# gate.net
KiCad netlist of a schematic drawn in EAGLE
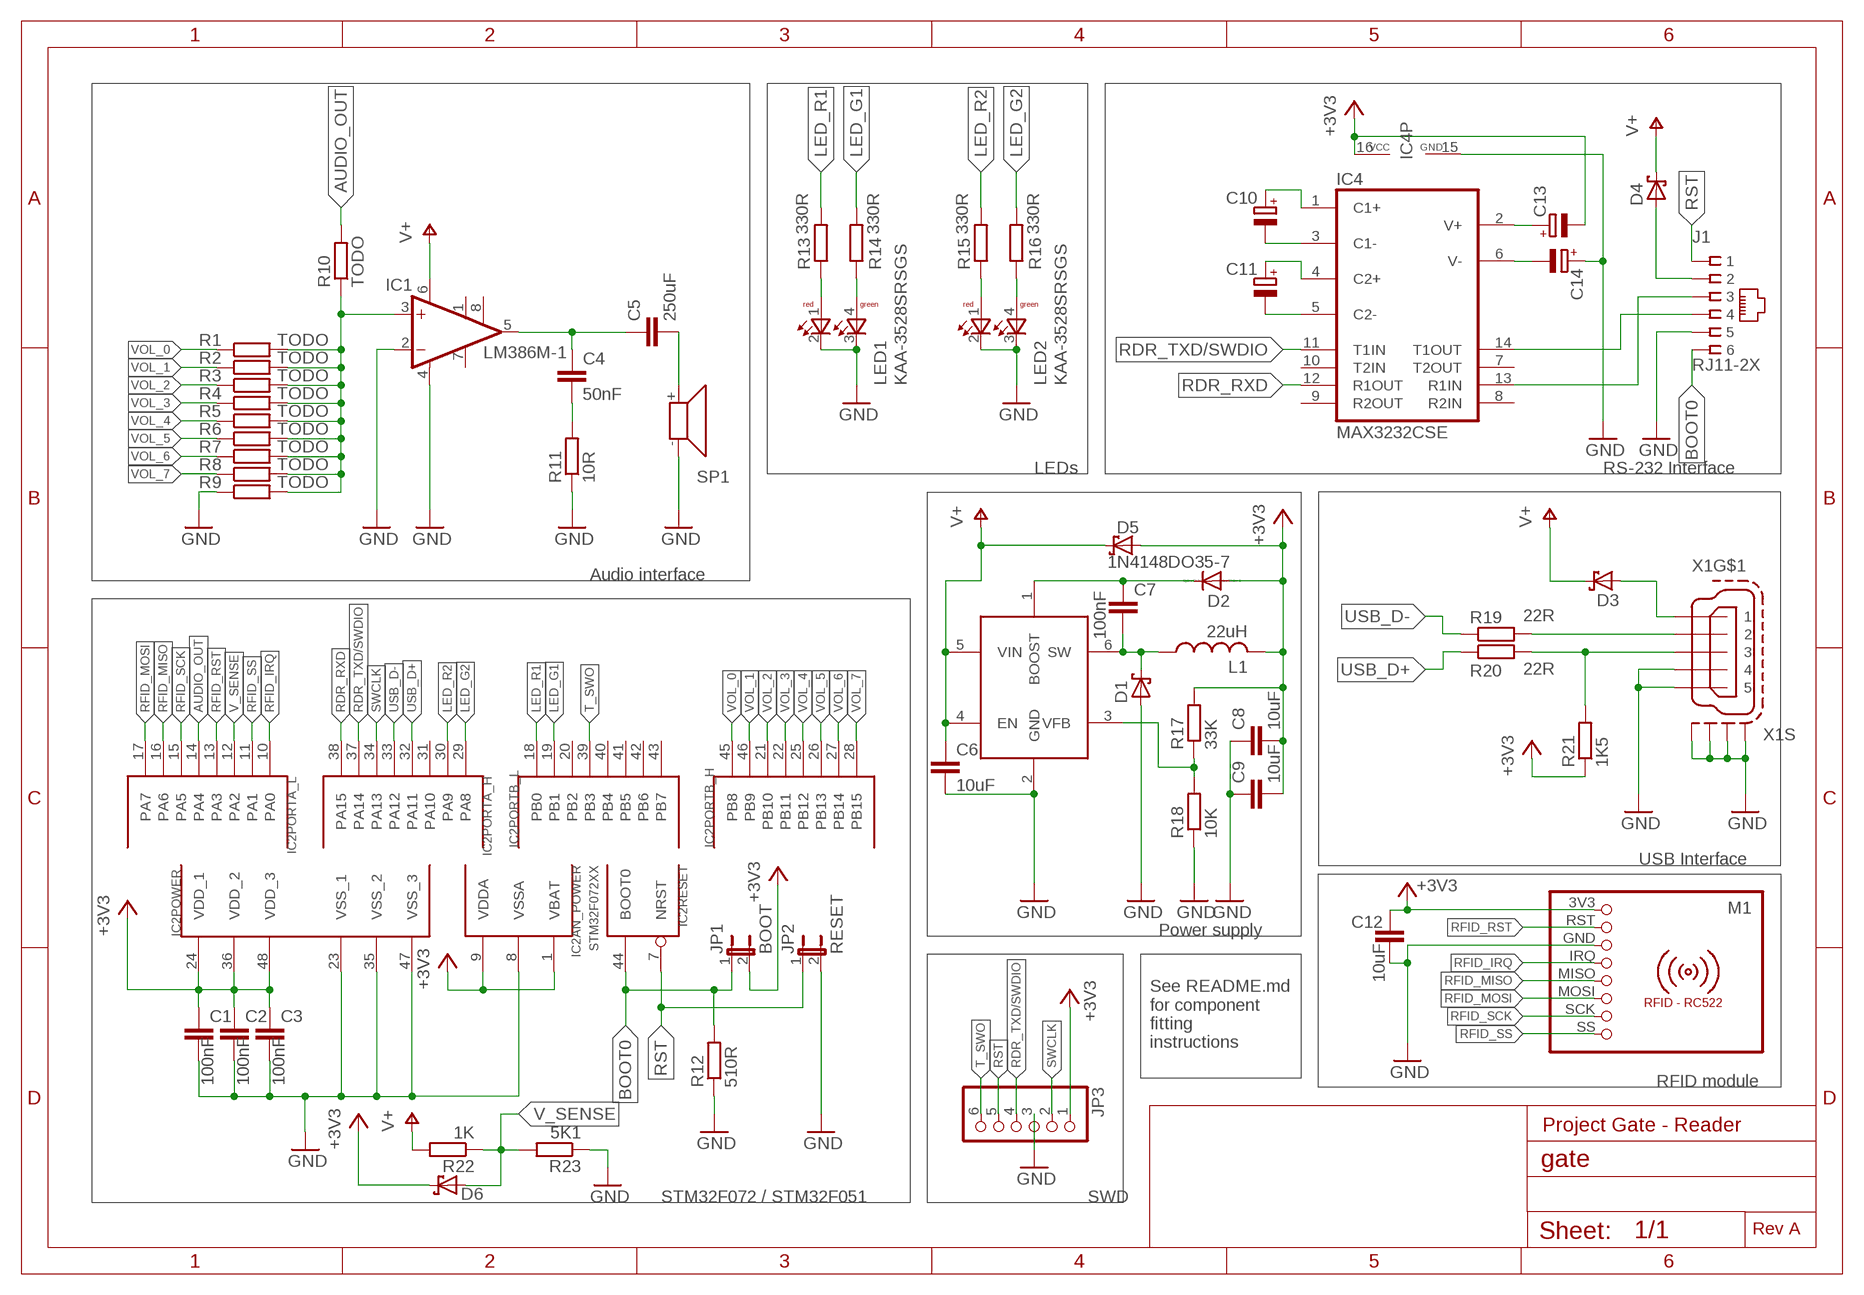
[diagram p0: schematic, sheet 1]

(export (version "E")
  (design (tool "Eeschema 10.0.6"))
  (components
    (comp (ref "C1")
      (value "100nF")
      (footprint "eagle-import:C0805")
      (libsource (lib "eagle-import") (part "C-EUC0805"))
    )
    (comp (ref "C2")
      (value "100nF")
      (footprint "eagle-import:C0805")
      (libsource (lib "eagle-import") (part "C-EUC0805"))
    )
    (comp (ref "C3")
      (value "100nF")
      (footprint "eagle-import:C0805")
      (libsource (lib "eagle-import") (part "C-EUC0805"))
    )
    (comp (ref "C4")
      (value "50nF")
      (footprint "eagle-import:C0805")
      (libsource (lib "eagle-import") (part "C-EUC0805"))
    )
    (comp (ref "C5")
      (value "250uF")
      (footprint "eagle-import:C0805")
      (libsource (lib "eagle-import") (part "C-EUC0805"))
    )
    (comp (ref "C6")
      (value "10uF")
      (footprint "eagle-import:C3225")
      (libsource (lib "eagle-import") (part "C-EUC3225"))
    )
    (comp (ref "C7")
      (value "100nF")
      (footprint "eagle-import:C0805")
      (libsource (lib "eagle-import") (part "C-EUC0805"))
    )
    (comp (ref "C8")
      (value "10uF")
      (footprint "eagle-import:C0805")
      (libsource (lib "eagle-import") (part "C-EUC0805"))
    )
    (comp (ref "C9")
      (value "10uF")
      (footprint "eagle-import:C0805")
      (libsource (lib "eagle-import") (part "C-EUC0805"))
    )
    (comp (ref "C10")
      (value "CPOL-EU153CLV-0505")
      (footprint "eagle-import:153CLV-0505")
      (libsource (lib "eagle-import") (part "CPOL-EU153CLV-0505"))
    )
    (comp (ref "C11")
      (value "CPOL-EU153CLV-0505")
      (footprint "eagle-import:153CLV-0505")
      (libsource (lib "eagle-import") (part "CPOL-EU153CLV-0505"))
    )
    (comp (ref "C12")
      (value "10uF")
      (footprint "eagle-import:C0805")
      (libsource (lib "eagle-import") (part "C-EUC0805"))
    )
    (comp (ref "C13")
      (value "CPOL-EU153CLV-0505")
      (footprint "eagle-import:153CLV-0505")
      (libsource (lib "eagle-import") (part "CPOL-EU153CLV-0505"))
    )
    (comp (ref "C14")
      (value "CPOL-EU153CLV-0505")
      (footprint "eagle-import:153CLV-0505")
      (libsource (lib "eagle-import") (part "CPOL-EU153CLV-0505"))
    )
    (comp (ref "D1")
      (value "SCHOTTKY-DIODESMD")
      (footprint "eagle-import:SMB")
      (libsource (lib "eagle-import") (part "SCHOTTKY-DIODESMD"))
    )
    (comp (ref "D2")
      (value "1N4148DO35-7")
      (footprint "eagle-import:DO35-7")
      (libsource (lib "eagle-import") (part "1N4148DO35-7"))
    )
    (comp (ref "D3")
      (value "SCHOTTKY-DIODESMD")
      (footprint "eagle-import:SMB")
      (libsource (lib "eagle-import") (part "SCHOTTKY-DIODESMD"))
    )
    (comp (ref "D4")
      (value "SCHOTTKY-DIODESMD")
      (footprint "eagle-import:SMB")
      (libsource (lib "eagle-import") (part "SCHOTTKY-DIODESMD"))
    )
    (comp (ref "D5")
      (value "SCHOTTKY-DIODESMD")
      (footprint "eagle-import:SMB")
      (libsource (lib "eagle-import") (part "SCHOTTKY-DIODESMD"))
    )
    (comp (ref "D6")
      (value "SCHOTTKY-DIODESMD")
      (footprint "eagle-import:SMB")
      (libsource (lib "eagle-import") (part "SCHOTTKY-DIODESMD"))
    )
    (comp (ref "IC1")
      (value "LM386M-1")
      (footprint "eagle-import:SO08")
      (libsource (lib "eagle-import") (part "LM386?-M1"))
    )
    (comp (ref "IC2")
      (value "STM32F072XX")
      (footprint "eagle-import:TQFP48")
      (libsource (lib "eagle-import") (part "STM32F072XX"))
    )
    (comp (ref "IC3")
      (value "MCP16301/H")
      (footprint "eagle-import:SOT23-6")
      (libsource (lib "eagle-import") (part "MCP16301/H"))
    )
    (comp (ref "IC4")
      (value "MAX3232CSE")
      (footprint "eagle-import:SO16")
      (libsource (lib "eagle-import") (part "MAX3232SEC"))
    )
    (comp (ref "J1")
      (value "RJ11-2X")
      (footprint "eagle-import:RJ11-NO_SHIELD")
      (libsource (lib "eagle-import") (part "RJ11-2X"))
    )
    (comp (ref "JP1")
      (value "BOOT")
      (footprint "eagle-import:JP1")
      (libsource (lib "eagle-import") (part "JP1E"))
    )
    (comp (ref "JP2")
      (value "RESET")
      (footprint "eagle-import:JP1")
      (libsource (lib "eagle-import") (part "JP1E"))
    )
    (comp (ref "JP3")
      (value "PINHD-1X6")
      (footprint "eagle-import:1X06")
      (libsource (lib "eagle-import") (part "PINHD-1X6"))
    )
    (comp (ref "L1")
      (value "22uH")
      (footprint "eagle-import:PIS2816")
      (libsource (lib "eagle-import") (part "L-USPIS2816"))
    )
    (comp (ref "LED1")
      (value "KAA-3528SRSGS")
      (footprint "eagle-import:KAA-3528SRSGS")
      (libsource (lib "eagle-import") (part "KAA-3528SRSGS"))
    )
    (comp (ref "LED2")
      (value "KAA-3528SRSGS")
      (footprint "eagle-import:KAA-3528SRSGS")
      (libsource (lib "eagle-import") (part "KAA-3528SRSGS"))
    )
    (comp (ref "M1")
      (value "RFID-RC522")
      (footprint "eagle-import:RFID-RC522")
      (libsource (lib "eagle-import") (part "RFID-RC522"))
    )
    (comp (ref "R1")
      (value "TODO")
      (footprint "eagle-import:R0805")
      (libsource (lib "eagle-import") (part "R-EU_R0805"))
    )
    (comp (ref "R2")
      (value "TODO")
      (footprint "eagle-import:R0805")
      (libsource (lib "eagle-import") (part "R-EU_R0805"))
    )
    (comp (ref "R3")
      (value "TODO")
      (footprint "eagle-import:R0805")
      (libsource (lib "eagle-import") (part "R-EU_R0805"))
    )
    (comp (ref "R4")
      (value "TODO")
      (footprint "eagle-import:R0805")
      (libsource (lib "eagle-import") (part "R-EU_R0805"))
    )
    (comp (ref "R5")
      (value "TODO")
      (footprint "eagle-import:R0805")
      (libsource (lib "eagle-import") (part "R-EU_R0805"))
    )
    (comp (ref "R6")
      (value "TODO")
      (footprint "eagle-import:R0805")
      (libsource (lib "eagle-import") (part "R-EU_R0805"))
    )
    (comp (ref "R7")
      (value "TODO")
      (footprint "eagle-import:R0805")
      (libsource (lib "eagle-import") (part "R-EU_R0805"))
    )
    (comp (ref "R8")
      (value "TODO")
      (footprint "eagle-import:R0805")
      (libsource (lib "eagle-import") (part "R-EU_R0805"))
    )
    (comp (ref "R9")
      (value "TODO")
      (footprint "eagle-import:R0805")
      (libsource (lib "eagle-import") (part "R-EU_R0805"))
    )
    (comp (ref "R10")
      (value "TODO")
      (footprint "eagle-import:R0805")
      (libsource (lib "eagle-import") (part "R-EU_R0805"))
    )
    (comp (ref "R11")
      (value "10R")
      (footprint "eagle-import:R0805")
      (libsource (lib "eagle-import") (part "R-EU_R0805"))
    )
    (comp (ref "R12")
      (value "510R")
      (footprint "eagle-import:R0805")
      (libsource (lib "eagle-import") (part "R-EU_R0805"))
    )
    (comp (ref "R13")
      (value "330R")
      (footprint "eagle-import:R0805")
      (libsource (lib "eagle-import") (part "R-EU_R0805"))
    )
    (comp (ref "R14")
      (value "330R")
      (footprint "eagle-import:R0805")
      (libsource (lib "eagle-import") (part "R-EU_R0805"))
    )
    (comp (ref "R15")
      (value "330R")
      (footprint "eagle-import:R0805")
      (libsource (lib "eagle-import") (part "R-EU_R0805"))
    )
    (comp (ref "R16")
      (value "330R")
      (footprint "eagle-import:R0805")
      (libsource (lib "eagle-import") (part "R-EU_R0805"))
    )
    (comp (ref "R17")
      (value "33K")
      (footprint "eagle-import:R0805")
      (libsource (lib "eagle-import") (part "R-EU_R0805"))
    )
    (comp (ref "R18")
      (value "10K")
      (footprint "eagle-import:R0805")
      (libsource (lib "eagle-import") (part "R-EU_R0805"))
    )
    (comp (ref "R19")
      (value "22R")
      (footprint "eagle-import:R0805")
      (libsource (lib "eagle-import") (part "R-EU_R0805"))
    )
    (comp (ref "R20")
      (value "22R")
      (footprint "eagle-import:R0805")
      (libsource (lib "eagle-import") (part "R-EU_R0805"))
    )
    (comp (ref "R21")
      (value "1K5")
      (footprint "eagle-import:R0805")
      (libsource (lib "eagle-import") (part "R-EU_R0805"))
    )
    (comp (ref "R22")
      (value "1K")
      (footprint "eagle-import:R0805")
      (libsource (lib "eagle-import") (part "R-EU_R0805"))
    )
    (comp (ref "R23")
      (value "5K1")
      (footprint "eagle-import:R0805")
      (libsource (lib "eagle-import") (part "R-EU_R0805"))
    )
    (comp (ref "SP1")
      (value "SMS-1308MS-2-R")
      (footprint "eagle-import:SMS-1308MS-2-R")
      (libsource (lib "eagle-import") (part "SMS-1308MS-2-R"))
    )
    (comp (ref "X1")
      (value "MINI-USB-SCHIELD-32005-301")
      (footprint "eagle-import:32005-301")
      (libsource (lib "eagle-import") (part "MINI-USB-SCHIELD-32005-301"))
    )
  )
  (nets
    (net (code "1") (name "+3V3") (class "Default")
      (node (ref "C1") (pin "1") (pinfunction "1_1") (pintype "passive"))
      (node (ref "C12") (pin "1") (pinfunction "1_1") (pintype "passive"))
      (node (ref "C13") (pin "-") (pinfunction "-_-") (pintype "passive"))
      (node (ref "C2") (pin "1") (pinfunction "1_1") (pintype "passive"))
      (node (ref "C3") (pin "1") (pinfunction "1_1") (pintype "passive"))
      (node (ref "C8") (pin "2") (pinfunction "2_2") (pintype "passive"))
      (node (ref "C9") (pin "2") (pinfunction "2_2") (pintype "passive"))
      (node (ref "D2") (pin "A") (pinfunction "A_A") (pintype "passive"))
      (node (ref "D5") (pin "A") (pinfunction "A_A") (pintype "passive"))
      (node (ref "D6") (pin "C") (pinfunction "C_C") (pintype "passive"))
      (node (ref "IC2") (pin "1") (pinfunction "VBAT_1") (pintype "power_in"))
      (node (ref "IC2") (pin "24") (pinfunction "VDD_1_24") (pintype "power_in"))
      (node (ref "IC2") (pin "36") (pinfunction "VDD_2_36") (pintype "power_in"))
      (node (ref "IC2") (pin "48") (pinfunction "VDD_3_48") (pintype "power_in"))
      (node (ref "IC2") (pin "9") (pinfunction "VDDA_9") (pintype "power_in"))
      (node (ref "IC4") (pin "16") (pinfunction "VCC_16") (pintype "power_in"))
      (node (ref "JP1") (pin "2") (pinfunction "2_2") (pintype "passive"))
      (node (ref "JP3") (pin "1") (pinfunction "1_1") (pintype "passive"))
      (node (ref "L1") (pin "2") (pinfunction "2_2") (pintype "passive"))
      (node (ref "M1") (pin "3V3") (pinfunction "1_3V3") (pintype "passive"))
      (node (ref "R17") (pin "2") (pinfunction "2_2") (pintype "passive"))
      (node (ref "R21") (pin "1") (pinfunction "1_1") (pintype "passive"))
    )
    (net (code "2") (name "AUDIO_OUT") (class "Default")
      (node (ref "IC2") (pin "14") (pinfunction "PA4_14") (pintype "bidirectional"))
      (node (ref "R10") (pin "2") (pinfunction "2_2") (pintype "passive"))
    )
    (net (code "3") (name "BOOT0") (class "Default")
      (node (ref "IC2") (pin "44") (pinfunction "BOOT0_44") (pintype "input"))
      (node (ref "J1") (pin "6") (pinfunction "6_6") (pintype "passive"))
      (node (ref "JP1") (pin "1") (pinfunction "1_1") (pintype "passive"))
      (node (ref "R12") (pin "2") (pinfunction "2_2") (pintype "passive"))
    )
    (net (code "4") (name "GND") (class "Default")
      (node (ref "C1") (pin "2") (pinfunction "2_2") (pintype "passive"))
      (node (ref "C12") (pin "2") (pinfunction "2_2") (pintype "passive"))
      (node (ref "C14") (pin "+") (pinfunction "+_+") (pintype "passive"))
      (node (ref "C2") (pin "2") (pinfunction "2_2") (pintype "passive"))
      (node (ref "C3") (pin "2") (pinfunction "2_2") (pintype "passive"))
      (node (ref "C6") (pin "2") (pinfunction "2_2") (pintype "passive"))
      (node (ref "C8") (pin "1") (pinfunction "1_1") (pintype "passive"))
      (node (ref "C9") (pin "1") (pinfunction "1_1") (pintype "passive"))
      (node (ref "D1") (pin "A") (pinfunction "A_A") (pintype "passive"))
      (node (ref "IC1") (pin "2") (pinfunction "-IN_2") (pintype "input"))
      (node (ref "IC1") (pin "4") (pinfunction "GND_4") (pintype "power_in"))
      (node (ref "IC2") (pin "23") (pinfunction "VSS_1_23") (pintype "power_in"))
      (node (ref "IC2") (pin "35") (pinfunction "VSS_2_35") (pintype "power_in"))
      (node (ref "IC2") (pin "47") (pinfunction "VSS_3_47") (pintype "power_in"))
      (node (ref "IC2") (pin "8") (pinfunction "VSSA_8") (pintype "power_in"))
      (node (ref "IC3") (pin "2") (pinfunction "GND_2") (pintype "power_in"))
      (node (ref "IC4") (pin "15") (pinfunction "GND_15") (pintype "power_in"))
      (node (ref "J1") (pin "5") (pinfunction "5_5") (pintype "passive"))
      (node (ref "JP2") (pin "2") (pinfunction "2_2") (pintype "passive"))
      (node (ref "JP3") (pin "3") (pinfunction "3_3") (pintype "passive"))
      (node (ref "LED1") (pin "2") (pinfunction "C-RED_2") (pintype "passive"))
      (node (ref "LED1") (pin "3") (pinfunction "C-GREEN_3") (pintype "passive"))
      (node (ref "LED2") (pin "2") (pinfunction "C-RED_2") (pintype "passive"))
      (node (ref "LED2") (pin "3") (pinfunction "C-GREEN_3") (pintype "passive"))
      (node (ref "M1") (pin "GND") (pinfunction "3_GND") (pintype "passive"))
      (node (ref "R11") (pin "1") (pinfunction "1_1") (pintype "passive"))
      (node (ref "R12") (pin "1") (pinfunction "1_1") (pintype "passive"))
      (node (ref "R18") (pin "1") (pinfunction "1_1") (pintype "passive"))
      (node (ref "R23") (pin "1") (pinfunction "1_1") (pintype "passive"))
      (node (ref "R9") (pin "1") (pinfunction "1_1") (pintype "passive"))
      (node (ref "SP1") (pin "-") (pinfunction "2_-") (pintype "passive"))
      (node (ref "X1") (pin "4") (pinfunction "4_4") (pintype "passive"))
      (node (ref "X1") (pin "5") (pinfunction "5_5") (pintype "passive"))
      (node (ref "X1") (pin "M1") (pinfunction "S1_M1") (pintype "passive"))
      (node (ref "X1") (pin "M2") (pinfunction "S2_M2") (pintype "passive"))
      (node (ref "X1") (pin "M3") (pinfunction "S3_M3") (pintype "passive"))
      (node (ref "X1") (pin "M4") (pinfunction "S4_M4") (pintype "passive"))
    )
    (net (code "5") (name "LED_G1") (class "Default")
      (node (ref "IC2") (pin "19") (pinfunction "PB1_19") (pintype "bidirectional"))
      (node (ref "R14") (pin "2") (pinfunction "2_2") (pintype "passive"))
    )
    (net (code "6") (name "LED_G2") (class "Default")
      (node (ref "IC2") (pin "29") (pinfunction "PA8_29") (pintype "bidirectional"))
      (node (ref "R16") (pin "2") (pinfunction "2_2") (pintype "passive"))
    )
    (net (code "7") (name "LED_R1") (class "Default")
      (node (ref "IC2") (pin "18") (pinfunction "PB0_18") (pintype "bidirectional"))
      (node (ref "R13") (pin "2") (pinfunction "2_2") (pintype "passive"))
    )
    (net (code "8") (name "LED_R2") (class "Default")
      (node (ref "IC2") (pin "30") (pinfunction "PA9_30") (pintype "bidirectional"))
      (node (ref "R15") (pin "2") (pinfunction "2_2") (pintype "passive"))
    )
    (net (code "9") (name "Net-(C4-Pad2)") (class "Default")
      (node (ref "C4") (pin "2") (pinfunction "2_2") (pintype "passive"))
      (node (ref "R11") (pin "2") (pinfunction "2_2") (pintype "passive"))
    )
    (net (code "10") (name "Net-(D3-PadA)") (class "Default")
      (node (ref "D3") (pin "A") (pinfunction "A_A") (pintype "passive"))
      (node (ref "X1") (pin "1") (pinfunction "1_1") (pintype "passive"))
    )
    (net (code "11") (name "Net-(D4-PadA)") (class "Default")
      (node (ref "D4") (pin "A") (pinfunction "A_A") (pintype "passive"))
      (node (ref "J1") (pin "2") (pinfunction "2_2") (pintype "passive"))
    )
    (net (code "12") (name "Net-(IC1-+IN)") (class "Default")
      (node (ref "IC1") (pin "3") (pinfunction "+IN_3") (pintype "input"))
      (node (ref "R1") (pin "2") (pinfunction "2_2") (pintype "passive"))
      (node (ref "R10") (pin "1") (pinfunction "1_1") (pintype "passive"))
      (node (ref "R2") (pin "2") (pinfunction "2_2") (pintype "passive"))
      (node (ref "R3") (pin "2") (pinfunction "2_2") (pintype "passive"))
      (node (ref "R4") (pin "2") (pinfunction "2_2") (pintype "passive"))
      (node (ref "R5") (pin "2") (pinfunction "2_2") (pintype "passive"))
      (node (ref "R6") (pin "2") (pinfunction "2_2") (pintype "passive"))
      (node (ref "R7") (pin "2") (pinfunction "2_2") (pintype "passive"))
      (node (ref "R8") (pin "2") (pinfunction "2_2") (pintype "passive"))
      (node (ref "R9") (pin "2") (pinfunction "2_2") (pintype "passive"))
    )
    (net (code "13") (name "Net-(IC1-OUT)") (class "Default")
      (node (ref "C4") (pin "1") (pinfunction "1_1") (pintype "passive"))
      (node (ref "C5") (pin "1") (pinfunction "1_1") (pintype "passive"))
      (node (ref "IC1") (pin "5") (pinfunction "OUT_5") (pintype "output"))
    )
    (net (code "14") (name "Net-(IC3-BOOST)") (class "Default")
      (node (ref "C7") (pin "1") (pinfunction "1_1") (pintype "passive"))
      (node (ref "D2") (pin "C") (pinfunction "C_C") (pintype "passive"))
      (node (ref "IC3") (pin "1") (pinfunction "BOOST_1") (pintype "bidirectional"))
    )
    (net (code "15") (name "Net-(IC3-SW)") (class "Default")
      (node (ref "C7") (pin "2") (pinfunction "2_2") (pintype "passive"))
      (node (ref "D1") (pin "C") (pinfunction "C_C") (pintype "passive"))
      (node (ref "IC3") (pin "6") (pinfunction "SW_6") (pintype "power_in"))
      (node (ref "L1") (pin "1") (pinfunction "1_1") (pintype "passive"))
    )
    (net (code "16") (name "Net-(IC3-VFB)") (class "Default")
      (node (ref "IC3") (pin "3") (pinfunction "VFB_3") (pintype "bidirectional"))
      (node (ref "R17") (pin "1") (pinfunction "1_1") (pintype "passive"))
      (node (ref "R18") (pin "2") (pinfunction "2_2") (pintype "passive"))
    )
    (net (code "17") (name "Net-(IC4A-C1+)") (class "Default")
      (node (ref "C10") (pin "+") (pinfunction "+_+") (pintype "passive"))
      (node (ref "IC4") (pin "1") (pinfunction "C1+_1") (pintype "bidirectional"))
    )
    (net (code "18") (name "Net-(IC4A-C1-)") (class "Default")
      (node (ref "C10") (pin "-") (pinfunction "-_-") (pintype "passive"))
      (node (ref "IC4") (pin "3") (pinfunction "C1-_3") (pintype "bidirectional"))
    )
    (net (code "19") (name "Net-(IC4A-C2+)") (class "Default")
      (node (ref "C11") (pin "+") (pinfunction "+_+") (pintype "passive"))
      (node (ref "IC4") (pin "4") (pinfunction "C2+_4") (pintype "bidirectional"))
    )
    (net (code "20") (name "Net-(IC4A-C2-)") (class "Default")
      (node (ref "C11") (pin "-") (pinfunction "-_-") (pintype "passive"))
      (node (ref "IC4") (pin "5") (pinfunction "C2-_5") (pintype "bidirectional"))
    )
    (net (code "21") (name "Net-(IC4A-R1IN)") (class "Default")
      (node (ref "IC4") (pin "13") (pinfunction "R1IN_13") (pintype "input"))
      (node (ref "J1") (pin "3") (pinfunction "3_3") (pintype "passive"))
    )
    (net (code "22") (name "Net-(IC4A-T1OUT)") (class "Default")
      (node (ref "IC4") (pin "14") (pinfunction "T1OUT_14") (pintype "output"))
      (node (ref "J1") (pin "4") (pinfunction "4_4") (pintype "passive"))
    )
    (net (code "23") (name "Net-(IC4A-V+)") (class "Default")
      (node (ref "C13") (pin "+") (pinfunction "+_+") (pintype "passive"))
      (node (ref "IC4") (pin "2") (pinfunction "V+_2") (pintype "bidirectional"))
    )
    (net (code "24") (name "Net-(IC4A-V-)") (class "Default")
      (node (ref "C14") (pin "-") (pinfunction "-_-") (pintype "passive"))
      (node (ref "IC4") (pin "6") (pinfunction "V-_6") (pintype "bidirectional"))
    )
    (net (code "25") (name "Net-(LED1-A-GREEN)") (class "Default")
      (node (ref "LED1") (pin "4") (pinfunction "A-GREEN_4") (pintype "passive"))
      (node (ref "R14") (pin "1") (pinfunction "1_1") (pintype "passive"))
    )
    (net (code "26") (name "Net-(LED1-A-RED)") (class "Default")
      (node (ref "LED1") (pin "1") (pinfunction "A-RED_1") (pintype "passive"))
      (node (ref "R13") (pin "1") (pinfunction "1_1") (pintype "passive"))
    )
    (net (code "27") (name "Net-(LED2-A-GREEN)") (class "Default")
      (node (ref "LED2") (pin "4") (pinfunction "A-GREEN_4") (pintype "passive"))
      (node (ref "R16") (pin "1") (pinfunction "1_1") (pintype "passive"))
    )
    (net (code "28") (name "Net-(LED2-A-RED)") (class "Default")
      (node (ref "LED2") (pin "1") (pinfunction "A-RED_1") (pintype "passive"))
      (node (ref "R15") (pin "1") (pinfunction "1_1") (pintype "passive"))
    )
    (net (code "29") (name "Net-(R19-Pad2)") (class "Default")
      (node (ref "R19") (pin "2") (pinfunction "2_2") (pintype "passive"))
      (node (ref "X1") (pin "2") (pinfunction "2_2") (pintype "passive"))
    )
    (net (code "30") (name "Net-(R20-Pad2)") (class "Default")
      (node (ref "R20") (pin "2") (pinfunction "2_2") (pintype "passive"))
      (node (ref "R21") (pin "2") (pinfunction "2_2") (pintype "passive"))
      (node (ref "X1") (pin "3") (pinfunction "3_3") (pintype "passive"))
    )
    (net (code "31") (name "Net-(SP1-1)") (class "Default")
      (node (ref "C5") (pin "2") (pinfunction "2_2") (pintype "passive"))
      (node (ref "SP1") (pin "+") (pinfunction "1_+") (pintype "passive"))
    )
    (net (code "32") (name "RDR_RXD") (class "Default")
      (node (ref "IC2") (pin "38") (pinfunction "PA15_38") (pintype "bidirectional"))
      (node (ref "IC4") (pin "12") (pinfunction "R1OUT_12") (pintype "output"))
    )
    (net (code "33") (name "RDR_TXD{slash}SWDIO") (class "Default")
      (node (ref "IC2") (pin "37") (pinfunction "PA14_37") (pintype "bidirectional"))
      (node (ref "IC4") (pin "11") (pinfunction "T1IN_11") (pintype "input"))
      (node (ref "JP3") (pin "4") (pinfunction "4_4") (pintype "passive"))
    )
    (net (code "34") (name "RFID_IRQ") (class "Default")
      (node (ref "IC2") (pin "10") (pinfunction "PA0_10") (pintype "bidirectional"))
      (node (ref "M1") (pin "IRQ") (pinfunction "4_IRQ") (pintype "passive"))
    )
    (net (code "35") (name "RFID_MISO") (class "Default")
      (node (ref "IC2") (pin "16") (pinfunction "PA6_16") (pintype "bidirectional"))
      (node (ref "M1") (pin "MISO") (pinfunction "5_MISO") (pintype "passive"))
    )
    (net (code "36") (name "RFID_MOSI") (class "Default")
      (node (ref "IC2") (pin "17") (pinfunction "PA7_17") (pintype "bidirectional"))
      (node (ref "M1") (pin "MOSI") (pinfunction "6_MOSI") (pintype "passive"))
    )
    (net (code "37") (name "RFID_RST") (class "Default")
      (node (ref "IC2") (pin "13") (pinfunction "PA3_13") (pintype "bidirectional"))
      (node (ref "M1") (pin "RST") (pinfunction "2_RST") (pintype "passive"))
    )
    (net (code "38") (name "RFID_SCK") (class "Default")
      (node (ref "IC2") (pin "15") (pinfunction "PA5_15") (pintype "bidirectional"))
      (node (ref "M1") (pin "SCK") (pinfunction "7_SCK") (pintype "passive"))
    )
    (net (code "39") (name "RFID_SS") (class "Default")
      (node (ref "IC2") (pin "11") (pinfunction "PA1_11") (pintype "bidirectional"))
      (node (ref "M1") (pin "SS") (pinfunction "8_SS") (pintype "passive"))
    )
    (net (code "40") (name "RST") (class "Default")
      (node (ref "IC2") (pin "7") (pinfunction "NRST_7") (pintype "input"))
      (node (ref "J1") (pin "1") (pinfunction "1_1") (pintype "passive"))
      (node (ref "JP2") (pin "1") (pinfunction "1_1") (pintype "passive"))
      (node (ref "JP3") (pin "5") (pinfunction "5_5") (pintype "passive"))
    )
    (net (code "41") (name "SWCLK") (class "Default")
      (node (ref "IC2") (pin "34") (pinfunction "PA13_34") (pintype "bidirectional"))
      (node (ref "JP3") (pin "2") (pinfunction "2_2") (pintype "passive"))
    )
    (net (code "42") (name "T_SWO") (class "Default")
      (node (ref "IC2") (pin "39") (pinfunction "PB3_39") (pintype "bidirectional"))
      (node (ref "JP3") (pin "6") (pinfunction "6_6") (pintype "passive"))
    )
    (net (code "43") (name "USB_D+") (class "Default")
      (node (ref "IC2") (pin "32") (pinfunction "PA11_32") (pintype "bidirectional"))
      (node (ref "R20") (pin "1") (pinfunction "1_1") (pintype "passive"))
    )
    (net (code "44") (name "USB_D-") (class "Default")
      (node (ref "IC2") (pin "33") (pinfunction "PA12_33") (pintype "bidirectional"))
      (node (ref "R19") (pin "1") (pinfunction "1_1") (pintype "passive"))
    )
    (net (code "45") (name "V+") (class "Default")
      (node (ref "C6") (pin "1") (pinfunction "1_1") (pintype "passive"))
      (node (ref "D3") (pin "C") (pinfunction "C_C") (pintype "passive"))
      (node (ref "D4") (pin "C") (pinfunction "C_C") (pintype "passive"))
      (node (ref "D5") (pin "C") (pinfunction "C_C") (pintype "passive"))
      (node (ref "IC1") (pin "6") (pinfunction "VS_6") (pintype "power_in"))
      (node (ref "IC3") (pin "4") (pinfunction "EN_4") (pintype "bidirectional"))
      (node (ref "IC3") (pin "5") (pinfunction "VIN_5") (pintype "power_in"))
      (node (ref "R22") (pin "2") (pinfunction "2_2") (pintype "passive"))
    )
    (net (code "46") (name "VOL_0") (class "Default")
      (node (ref "IC2") (pin "45") (pinfunction "PB8_45") (pintype "bidirectional"))
      (node (ref "R1") (pin "1") (pinfunction "1_1") (pintype "passive"))
    )
    (net (code "47") (name "VOL_1") (class "Default")
      (node (ref "IC2") (pin "46") (pinfunction "PB9_46") (pintype "bidirectional"))
      (node (ref "R2") (pin "1") (pinfunction "1_1") (pintype "passive"))
    )
    (net (code "48") (name "VOL_2") (class "Default")
      (node (ref "IC2") (pin "21") (pinfunction "PB10_21") (pintype "bidirectional"))
      (node (ref "R3") (pin "1") (pinfunction "1_1") (pintype "passive"))
    )
    (net (code "49") (name "VOL_3") (class "Default")
      (node (ref "IC2") (pin "22") (pinfunction "PB11_22") (pintype "bidirectional"))
      (node (ref "R4") (pin "1") (pinfunction "1_1") (pintype "passive"))
    )
    (net (code "50") (name "VOL_4") (class "Default")
      (node (ref "IC2") (pin "25") (pinfunction "PB12_25") (pintype "bidirectional"))
      (node (ref "R5") (pin "1") (pinfunction "1_1") (pintype "passive"))
    )
    (net (code "51") (name "VOL_5") (class "Default")
      (node (ref "IC2") (pin "26") (pinfunction "PB13_26") (pintype "bidirectional"))
      (node (ref "R6") (pin "1") (pinfunction "1_1") (pintype "passive"))
    )
    (net (code "52") (name "VOL_6") (class "Default")
      (node (ref "IC2") (pin "27") (pinfunction "PB14_27") (pintype "bidirectional"))
      (node (ref "R7") (pin "1") (pinfunction "1_1") (pintype "passive"))
    )
    (net (code "53") (name "VOL_7") (class "Default")
      (node (ref "IC2") (pin "28") (pinfunction "PB15_28") (pintype "bidirectional"))
      (node (ref "R8") (pin "1") (pinfunction "1_1") (pintype "passive"))
    )
    (net (code "54") (name "V_SENSE") (class "Default")
      (node (ref "D6") (pin "A") (pinfunction "A_A") (pintype "passive"))
      (node (ref "IC2") (pin "12") (pinfunction "PA2_12") (pintype "bidirectional"))
      (node (ref "R22") (pin "1") (pinfunction "1_1") (pintype "passive"))
      (node (ref "R23") (pin "2") (pinfunction "2_2") (pintype "passive"))
    )
    (net (code "55") (name "unconnected-(IC1-BYPASS-Pad7)") (class "Default")
      (node (ref "IC1") (pin "7") (pinfunction "BYPASS_7") (pintype "passive"))
    )
    (net (code "56") (name "unconnected-(IC1-GAIN-Pad1)") (class "Default")
      (node (ref "IC1") (pin "1") (pinfunction "GAIN_1") (pintype "passive"))
    )
    (net (code "57") (name "unconnected-(IC1-GAIN-Pad8)") (class "Default")
      (node (ref "IC1") (pin "8") (pinfunction "GAIN_8") (pintype "passive"))
    )
    (net (code "58") (name "unconnected-(IC2B-PA10-Pad31)") (class "Default")
      (node (ref "IC2") (pin "31") (pinfunction "PA10_31") (pintype "bidirectional"))
    )
    (net (code "59") (name "unconnected-(IC2E-PB2-Pad20)") (class "Default")
      (node (ref "IC2") (pin "20") (pinfunction "PB2_20") (pintype "bidirectional"))
    )
    (net (code "60") (name "unconnected-(IC2E-PB4-Pad40)") (class "Default")
      (node (ref "IC2") (pin "40") (pinfunction "PB4_40") (pintype "bidirectional"))
    )
    (net (code "61") (name "unconnected-(IC2E-PB5-Pad41)") (class "Default")
      (node (ref "IC2") (pin "41") (pinfunction "PB5_41") (pintype "bidirectional"))
    )
    (net (code "62") (name "unconnected-(IC2E-PB6-Pad42)") (class "Default")
      (node (ref "IC2") (pin "42") (pinfunction "PB6_42") (pintype "bidirectional"))
    )
    (net (code "63") (name "unconnected-(IC2E-PB7-Pad43)") (class "Default")
      (node (ref "IC2") (pin "43") (pinfunction "PB7_43") (pintype "bidirectional"))
    )
    (net (code "64") (name "unconnected-(IC4A-R2IN-Pad8)") (class "Default")
      (node (ref "IC4") (pin "8") (pinfunction "R2IN_8") (pintype "input"))
    )
    (net (code "65") (name "unconnected-(IC4A-R2OUT-Pad9)") (class "Default")
      (node (ref "IC4") (pin "9") (pinfunction "R2OUT_9") (pintype "output"))
    )
    (net (code "66") (name "unconnected-(IC4A-T2IN-Pad10)") (class "Default")
      (node (ref "IC4") (pin "10") (pinfunction "T2IN_10") (pintype "input"))
    )
    (net (code "67") (name "unconnected-(IC4A-T2OUT-Pad7)") (class "Default")
      (node (ref "IC4") (pin "7") (pinfunction "T2OUT_7") (pintype "output"))
    )
  )
)
